# attinier85-display-shield-mk-2_0.net
KiCad netlist of a schematic drawn in EAGLE
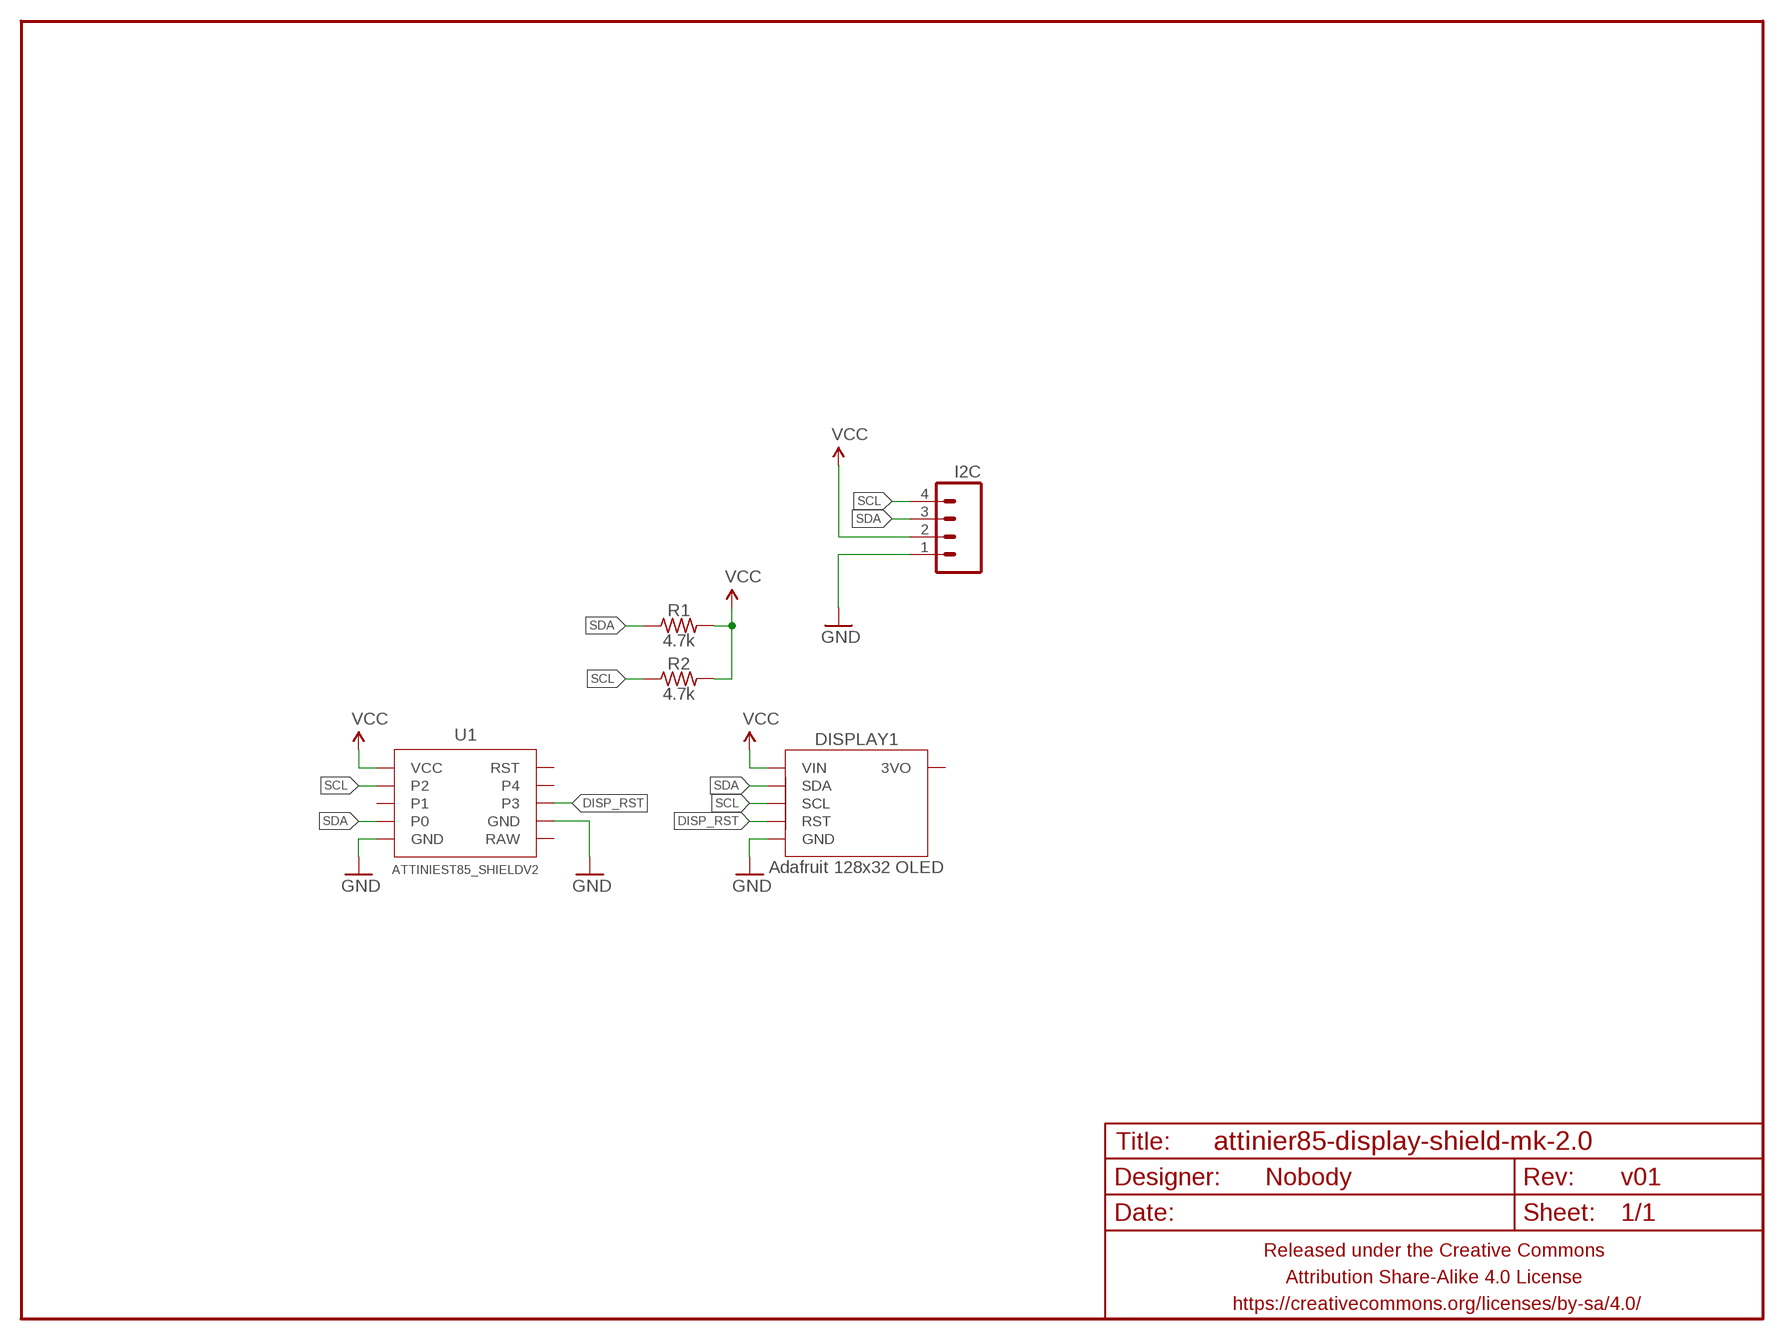
[diagram p0: schematic, sheet 1]

(export (version "E")
  (design (tool "Eeschema 10.0.6"))
  (components
    (comp (ref "DISPLAY1")
      (value "Adafruit 128x32 OLED")
      (footprint "eagle-import:ADAFRUIT_128X32_OLED_I2C_CLOSER_NOHOLES")
      (libsource (lib "eagle-import") (part "ADAFRUIT_128X32_OLED_I2CNOHOLES"))
    )
    (comp (ref "FRAME1")
      (value "FRAME-LETTERNO_PACKAGE")
      (footprint "eagle-import:DUMMY")
      (fields (field (name "DESIGNER") "Nobody"))
      (libsource (lib "eagle-import") (part "FRAME-LETTERNO_PACKAGE"))
    )
    (comp (ref "I2C")
      (value "M04PTH")
      (footprint "eagle-import:1X04-PTH-VERT")
      (libsource (lib "eagle-import") (part "M04PTH"))
    )
    (comp (ref "R1")
      (value "4.7k")
      (footprint "eagle-import:RESISTOR-AXIAL-PTH-7.62MM")
      (libsource (lib "eagle-import") (part "RESISTORPTH-AXIAL-7.62MM"))
    )
    (comp (ref "R2")
      (value "4.7k")
      (footprint "eagle-import:RESISTOR-AXIAL-PTH-7.62MM")
      (libsource (lib "eagle-import") (part "RESISTORPTH-AXIAL-7.62MM"))
    )
    (comp (ref "U1")
      (value "ATTINIEST85_SHIELDV2")
      (footprint "eagle-import:ATTINIEST85_SHIELD_V2")
      (libsource (lib "eagle-import") (part "ATTINIEST85_SHIELDV2"))
    )
  )
  (nets
    (net (code "1") (name "DISP_RST") (class "Default")
      (node (ref "DISPLAY1") (pin "RST") (pinfunction "RST_RST") (pintype "bidirectional"))
      (node (ref "U1") (pin "3") (pinfunction "P3_3") (pintype "bidirectional"))
    )
    (net (code "2") (name "GND") (class "Default")
      (node (ref "DISPLAY1") (pin "GND") (pinfunction "GND_GND") (pintype "bidirectional"))
      (node (ref "I2C") (pin "1") (pinfunction "1_1") (pintype "passive"))
      (node (ref "U1") (pin "GND@1") (pinfunction "GND_GND@1") (pintype "bidirectional"))
      (node (ref "U1") (pin "GND@2") (pinfunction "GND_GND@2") (pintype "bidirectional"))
    )
    (net (code "3") (name "SCL") (class "Default")
      (node (ref "DISPLAY1") (pin "SCL") (pinfunction "SCL_SCL") (pintype "bidirectional"))
      (node (ref "I2C") (pin "4") (pinfunction "4_4") (pintype "passive"))
      (node (ref "R2") (pin "P$1") (pinfunction "1_P$1") (pintype "passive"))
      (node (ref "U1") (pin "2") (pinfunction "P2_2") (pintype "bidirectional"))
    )
    (net (code "4") (name "SDA") (class "Default")
      (node (ref "DISPLAY1") (pin "SDA") (pinfunction "SDA_SDA") (pintype "bidirectional"))
      (node (ref "I2C") (pin "3") (pinfunction "3_3") (pintype "passive"))
      (node (ref "R1") (pin "P$1") (pinfunction "1_P$1") (pintype "passive"))
      (node (ref "U1") (pin "0") (pinfunction "P0_0") (pintype "bidirectional"))
    )
    (net (code "5") (name "VCC") (class "Default")
      (node (ref "DISPLAY1") (pin "VIN") (pinfunction "VIN_VIN") (pintype "bidirectional"))
      (node (ref "I2C") (pin "2") (pinfunction "2_2") (pintype "passive"))
      (node (ref "R1") (pin "P$2") (pinfunction "2_P$2") (pintype "passive"))
      (node (ref "R2") (pin "P$2") (pinfunction "2_P$2") (pintype "passive"))
      (node (ref "U1") (pin "VCC") (pinfunction "VCC_VCC") (pintype "bidirectional"))
    )
    (net (code "6") (name "unconnected-(DISPLAY1-Pad3VO)") (class "Default")
      (node (ref "DISPLAY1") (pin "3VO") (pinfunction "3VO_3VO") (pintype "bidirectional"))
    )
    (net (code "7") (name "unconnected-(U1-P1-Pad1)") (class "Default")
      (node (ref "U1") (pin "1") (pinfunction "P1_1") (pintype "bidirectional"))
    )
    (net (code "8") (name "unconnected-(U1-P4-Pad4)") (class "Default")
      (node (ref "U1") (pin "4") (pinfunction "P4_4") (pintype "bidirectional"))
    )
    (net (code "9") (name "unconnected-(U1-PadRAW)") (class "Default")
      (node (ref "U1") (pin "RAW") (pinfunction "RAW_RAW") (pintype "bidirectional"))
    )
    (net (code "10") (name "unconnected-(U1-PadRST)") (class "Default")
      (node (ref "U1") (pin "RST") (pinfunction "RST_RST") (pintype "bidirectional"))
    )
  )
)
